# half-pint-turbidimeter_controls_2_0_1__O.net
KiCad netlist of a schematic drawn in EAGLE
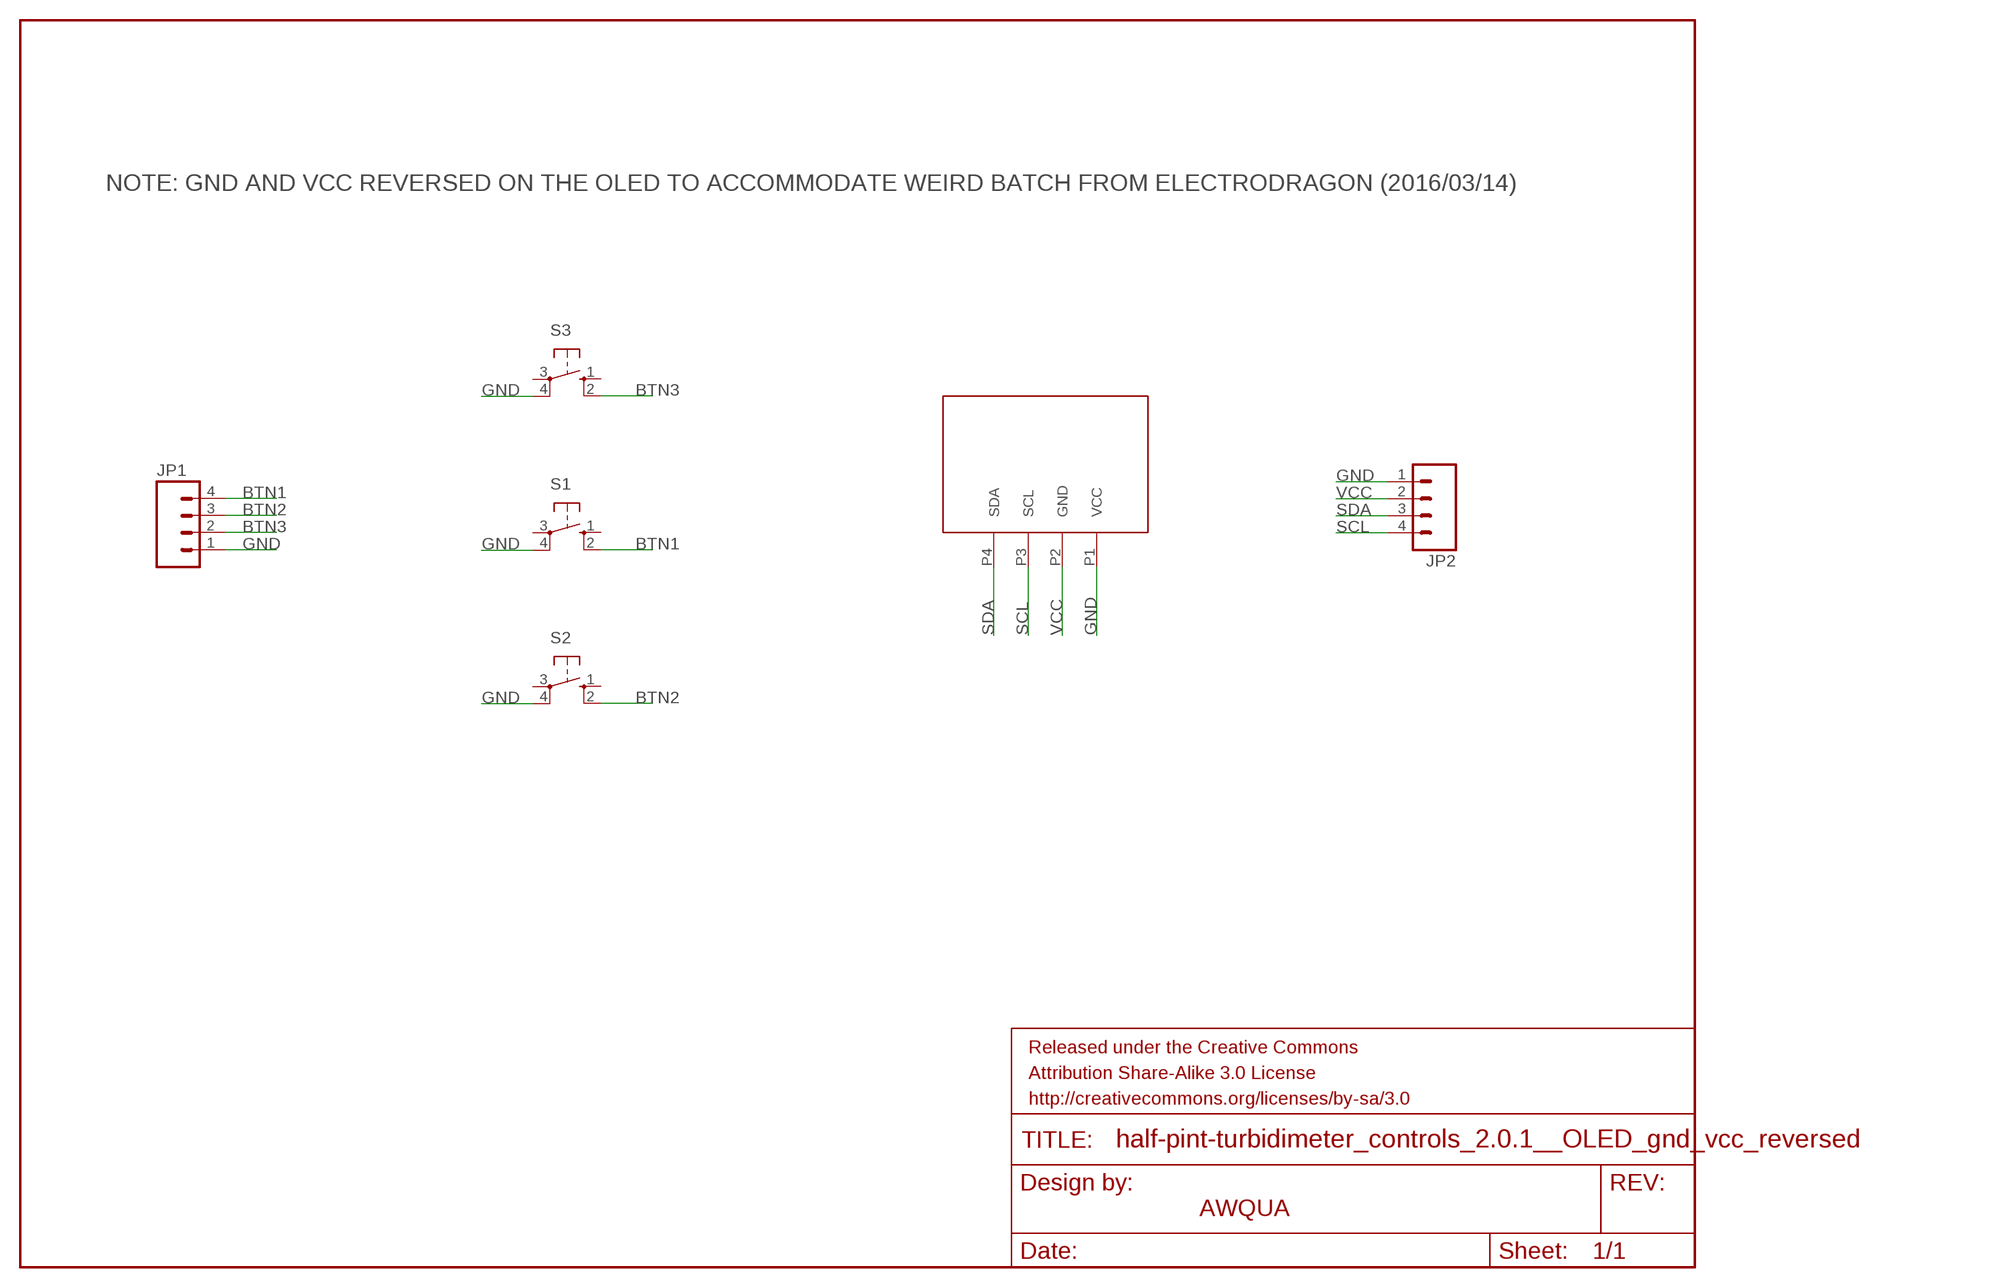
[diagram p0: schematic, sheet 1]

(export (version "E")
  (design (tool "Eeschema 10.0.6"))
  (components
    (comp (ref "FRAME1")
      (value "FRAME-LETTER")
      (footprint "eagle-import:CREATIVE_COMMONS")
      (libsource (lib "eagle-import") (part "FRAME-LETTER"))
    )
    (comp (ref "JP1")
      (value "M04PTH")
      (footprint "eagle-import:1X04")
      (libsource (lib "eagle-import") (part "M04PTH"))
    )
    (comp (ref "JP2")
      (value "M04PTH")
      (footprint "eagle-import:1X04")
      (libsource (lib "eagle-import") (part "M04PTH"))
    )
    (comp (ref "S1")
      (value "40-XX")
      (footprint "eagle-import:B3F-40XX")
      (fields (field (name "MF") "OMRON COMPONENTS USA") (field (name "MPN") "B3F-4000"))
      (libsource (lib "eagle-import") (part "40-XX"))
    )
    (comp (ref "S2")
      (value "40-XX")
      (footprint "eagle-import:B3F-40XX")
      (fields (field (name "MF") "OMRON COMPONENTS USA") (field (name "MPN") "B3F-4000"))
      (libsource (lib "eagle-import") (part "40-XX"))
    )
    (comp (ref "S3")
      (value "40-XX")
      (footprint "eagle-import:B3F-40XX")
      (fields (field (name "MF") "OMRON COMPONENTS USA") (field (name "MPN") "B3F-4000"))
      (libsource (lib "eagle-import") (part "40-XX"))
    )
    (comp (ref "U$2")
      (value "I2C-OLED-096")
      (footprint "eagle-import:I2C-OLED-096")
      (libsource (lib "eagle-import") (part "I2C-OLED-096"))
    )
  )
  (nets
    (net (code "1") (name "/BTN1") (class "Default")
      (node (ref "JP1") (pin "4") (pinfunction "4_4") (pintype "passive"))
      (node (ref "S1") (pin "2") (pinfunction "S1_2") (pintype "passive"))
    )
    (net (code "2") (name "/BTN2") (class "Default")
      (node (ref "JP1") (pin "3") (pinfunction "3_3") (pintype "passive"))
      (node (ref "S2") (pin "2") (pinfunction "S1_2") (pintype "passive"))
    )
    (net (code "3") (name "/BTN3") (class "Default")
      (node (ref "JP1") (pin "2") (pinfunction "2_2") (pintype "passive"))
      (node (ref "S3") (pin "2") (pinfunction "S1_2") (pintype "passive"))
    )
    (net (code "4") (name "/GND") (class "Default")
      (node (ref "JP1") (pin "1") (pinfunction "1_1") (pintype "passive"))
      (node (ref "JP2") (pin "1") (pinfunction "1_1") (pintype "passive"))
      (node (ref "S1") (pin "4") (pinfunction "P1_4") (pintype "passive"))
      (node (ref "S2") (pin "4") (pinfunction "P1_4") (pintype "passive"))
      (node (ref "S3") (pin "4") (pinfunction "P1_4") (pintype "passive"))
      (node (ref "U$2") (pin "P1") (pinfunction "VCC_P1") (pintype "bidirectional"))
    )
    (net (code "5") (name "/SCL") (class "Default")
      (node (ref "JP2") (pin "4") (pinfunction "4_4") (pintype "passive"))
      (node (ref "U$2") (pin "P3") (pinfunction "SCL_P3") (pintype "bidirectional"))
    )
    (net (code "6") (name "/SDA") (class "Default")
      (node (ref "JP2") (pin "3") (pinfunction "3_3") (pintype "passive"))
      (node (ref "U$2") (pin "P4") (pinfunction "SDA_P4") (pintype "bidirectional"))
    )
    (net (code "7") (name "/VCC") (class "Default")
      (node (ref "JP2") (pin "2") (pinfunction "2_2") (pintype "passive"))
      (node (ref "U$2") (pin "P2") (pinfunction "GND_P2") (pintype "bidirectional"))
    )
    (net (code "8") (name "unconnected-(S1-P-Pad3)") (class "Default")
      (node (ref "S1") (pin "3") (pinfunction "P_3") (pintype "passive"))
    )
    (net (code "9") (name "unconnected-(S1-S-Pad1)") (class "Default")
      (node (ref "S1") (pin "1") (pinfunction "S_1") (pintype "passive"))
    )
    (net (code "10") (name "unconnected-(S2-P-Pad3)") (class "Default")
      (node (ref "S2") (pin "3") (pinfunction "P_3") (pintype "passive"))
    )
    (net (code "11") (name "unconnected-(S2-S-Pad1)") (class "Default")
      (node (ref "S2") (pin "1") (pinfunction "S_1") (pintype "passive"))
    )
    (net (code "12") (name "unconnected-(S3-P-Pad3)") (class "Default")
      (node (ref "S3") (pin "3") (pinfunction "P_3") (pintype "passive"))
    )
    (net (code "13") (name "unconnected-(S3-S-Pad1)") (class "Default")
      (node (ref "S3") (pin "1") (pinfunction "S_1") (pintype "passive"))
    )
  )
)
